# Transmitter-2_4GHz.net
KiCad netlist of a schematic drawn in Altium Designer
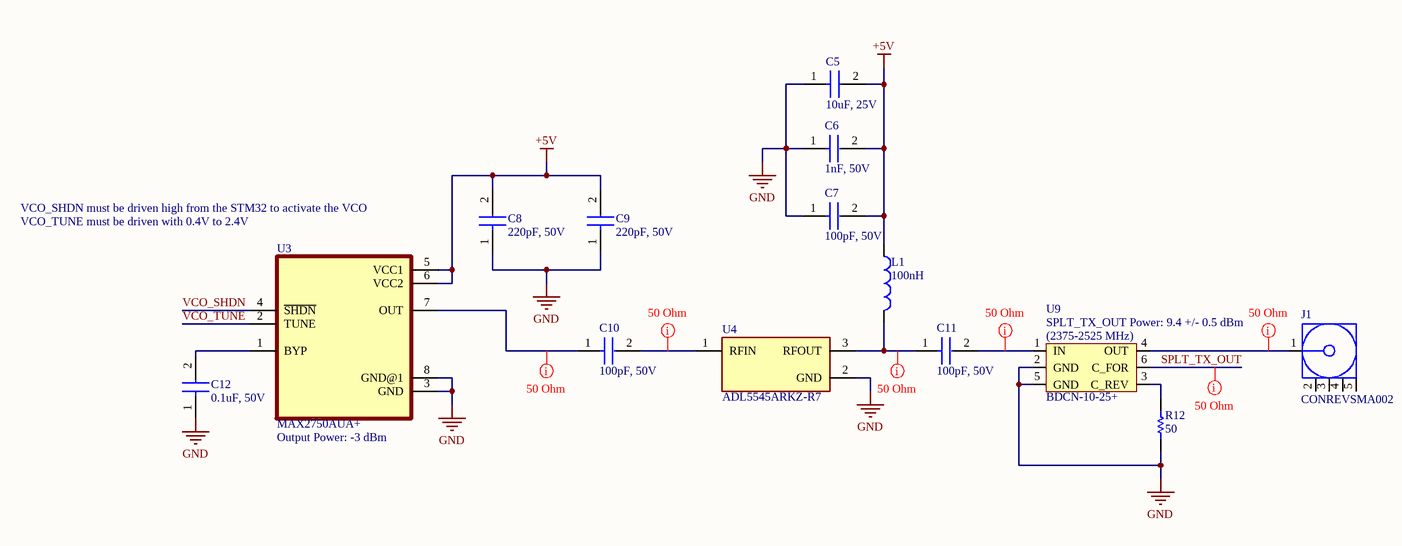
[diagram p0: Transmitter-2.4GHz.SchDoc]

(export (version "E")
  (design (tool "Eeschema 10.0.6"))
  (components
    (comp (ref "C5")
      (value "10uF, 25V")
      (footprint "CAP_CL31_SAM")
      (fields
        (field (name "MANUFACTURER") "Samsung")
        (field (name "MANUFACTURER PART NUMBER") "CL31B106KAHNNNE")
      )
      (libsource (lib "FMCW-Radar-v1") (part "CL31B106KAHNNNE"))
    )
    (comp (ref "C6")
      (value "1nF, 50V")
      (footprint "FP-0603-L_1_6_0_15-W_0_81-IPC_C")
      (fields
        (field (name "MANUFACTURER") "Kyocera AVX")
        (field (name "MANUFACTURER PART NUMBER") "06035A102JAT2A")
      )
      (libsource (lib "FMCW-Radar-v1") (part "06035A102JAT2A"))
    )
    (comp (ref "C7")
      (value "100pF, 50V")
      (footprint "CAPC17595_87N_KEM")
      (fields
        (field (name "MANUFACTURER") "KEMET")
        (field (name "MANUFACTURER PART NUMBER") "C0603C101J5GACTU")
      )
      (libsource (lib "FMCW-Radar-v1") (part "C0603C101J5GACTU"))
    )
    (comp (ref "C8")
      (value "220pF, 50V")
      (footprint "CAPC17595_87N_KEM")
      (fields
        (field (name "MANUFACTURER") "KEMET")
        (field (name "MANUFACTURER PART NUMBER") "C0603C221J5GAC7411")
      )
      (libsource (lib "FMCW-Radar-v1") (part "C0603C221J5GAC7411"))
    )
    (comp (ref "C9")
      (value "220pF, 50V")
      (footprint "CAPC17595_87N_KEM")
      (fields
        (field (name "MANUFACTURER") "KEMET")
        (field (name "MANUFACTURER PART NUMBER") "C0603C221J5GAC7411")
      )
      (libsource (lib "FMCW-Radar-v1") (part "C0603C221J5GAC7411"))
    )
    (comp (ref "C10")
      (value "100pF, 50V")
      (footprint "CAP_CC0402_YAG")
      (fields
        (field (name "MANUFACTURER") "Yageo")
        (field (name "MANUFACTURER PART NUMBER") "CC0402JRNPO9BN101")
      )
      (libsource (lib "FMCW-Radar-v1") (part "CC0402JRNPO9BN101"))
    )
    (comp (ref "C11")
      (value "100pF, 50V")
      (footprint "CAP_CC0402_YAG")
      (fields
        (field (name "MANUFACTURER") "Yageo")
        (field (name "MANUFACTURER PART NUMBER") "CC0402JRNPO9BN101")
      )
      (libsource (lib "FMCW-Radar-v1") (part "CC0402JRNPO9BN101"))
    )
    (comp (ref "C12")
      (value "0.1uF, 50V")
      (footprint "CAP_CC0603_YAG-M")
      (fields
        (field (name "MANUFACTURER") "Yageo")
        (field (name "MANUFACTURER PART NUMBER") "CC0603JRX7R9BB104")
      )
      (libsource (lib "FMCW-Radar-v1") (part "CC0603JRX7R9BB104"))
    )
    (comp (ref "J1")
      (value "CONREVSMA002")
      (footprint "CON-REVSMA-RA")
      (description "RF SMA Connector")
      (fields (field (name "MANUFACTURER") "Linx"))
      (libsource (lib "FMCW-Radar-v1") (part "CONREVSMA002"))
    )
    (comp (ref "L1")
      (value "100nH")
      (footprint "INDC1608X95N")
      (description "General Purpose Inductor, 0.1uH, 5%, 1 Element, Air-Core, SMD, 0603")
      (fields
        (field (name "MANUFACTURER") "Murata")
        (field (name "MANUFACTURER PART NUMBER") "LQG18HNR10J00D")
      )
      (libsource (lib "FMCW-Radar-v1") (part "LQG18HNR10J00D"))
    )
    (comp (ref "R12")
      (value "50")
      (footprint "RESC1005X35N")
      (description "Fixed Resistor, Thin Film, 0.0625W, 50ohm, 50V, 0.1% +/-Tol, 50ppm/Cel, Surface Mount, 0402")
      (fields
        (field (name "MANUFACTURER") "Yageo")
        (field (name "MANUFACTURER PART NUMBER") "RT0402BRE0750RL")
      )
      (libsource (lib "FMCW-Radar-v1") (part "RT0402BRE0750RL"))
    )
    (comp (ref "U3")
      (value "MAX2750AUA+")
      (footprint "SOP65P490X110-8N")
      (description "Voltage Controlled Oscillator, 2370MHz Min, 2470MHz Max")
      (fields (field (name "MANUFACTURER") "Maxim"))
      (libsource (lib "FMCW-Radar-v1") (part "MAX2750AUA+"))
    )
    (comp (ref "U4")
      (value "ADL5545ARKZ-R7")
      (footprint "ADL5545ARKZ-R7")
      (description "Wide Band Medium Power Amplifier, 30MHz Min, 6000MHz Max, 1 Func, BIPolar")
      (fields (field (name "MANUFACTURER") "Analog Devices"))
      (libsource (lib "FMCW-Radar-v1") (part "ADL5545ARKZ-R7"))
    )
    (comp (ref "U9")
      (value "BDCN-10-25+")
      (footprint "BDCN-10-25+")
      (description "Bi-Directional Coupler, 824MHz Min, 2525MHz Max, 1.5dB Insertion Loss-Max")
      (fields (field (name "MANUFACTURER") "Mini-Circuits"))
      (libsource (lib "FMCW-Radar-v1") (part "BDCN-10-25+"))
    )
  )
  (nets
    (net (code "1") (name "+5V") (class "Default")
      (node (ref "C5") (pin "2") (pinfunction "2_2") (pintype "passive"))
      (node (ref "C6") (pin "2") (pinfunction "2_2") (pintype "passive"))
      (node (ref "C7") (pin "2") (pinfunction "2_2") (pintype "passive"))
      (node (ref "C8") (pin "2") (pinfunction "2_2") (pintype "passive"))
      (node (ref "C9") (pin "2") (pinfunction "2_2") (pintype "passive"))
      (node (ref "L1") (pin "1") (pinfunction "1_1") (pintype "passive"))
      (node (ref "U3") (pin "5") (pinfunction "VCC1_5") (pintype "power_in"))
      (node (ref "U3") (pin "6") (pinfunction "VCC2_6") (pintype "power_in"))
    )
    (net (code "2") (name "/SPLT_TX_OUT") (class "Default")
      (node (ref "U9") (pin "6") (pinfunction "C_FOR_6") (pintype "passive"))
    )
    (net (code "3") (name "/VCO_SHDN") (class "Default")
      (node (ref "U3") (pin "4") (pinfunction "~{SHDN}_4") (pintype "passive"))
    )
    (net (code "4") (name "/VCO_TUNE") (class "Default")
      (node (ref "U3") (pin "2") (pinfunction "TUNE_2") (pintype "passive"))
    )
    (net (code "5") (name "GND") (class "Default")
      (node (ref "C12") (pin "1") (pinfunction "1_1") (pintype "passive"))
      (node (ref "C5") (pin "1") (pinfunction "1_1") (pintype "passive"))
      (node (ref "C6") (pin "1") (pinfunction "1_1") (pintype "passive"))
      (node (ref "C7") (pin "1") (pinfunction "1_1") (pintype "passive"))
      (node (ref "C8") (pin "1") (pinfunction "1_1") (pintype "passive"))
      (node (ref "C9") (pin "1") (pinfunction "1_1") (pintype "passive"))
      (node (ref "R12") (pin "1") (pinfunction "1_1") (pintype "passive"))
      (node (ref "U3") (pin "3") (pinfunction "GND_3") (pintype "power_in"))
      (node (ref "U3") (pin "8") (pinfunction "GND@1_8") (pintype "power_in"))
      (node (ref "U4") (pin "2") (pinfunction "GND_2") (pintype "passive"))
      (node (ref "U9") (pin "2") (pinfunction "GND_2") (pintype "passive"))
      (node (ref "U9") (pin "5") (pinfunction "GND_5") (pintype "passive"))
    )
    (net (code "6") (name "Net-(J1-Signal)") (class "Default")
      (node (ref "J1") (pin "1") (pinfunction "Signal_1") (pintype "passive"))
      (node (ref "U9") (pin "4") (pinfunction "OUT_4") (pintype "passive"))
    )
    (net (code "7") (name "Net-(U3-BYP)") (class "Default")
      (node (ref "C12") (pin "2") (pinfunction "2_2") (pintype "passive"))
      (node (ref "U3") (pin "1") (pinfunction "BYP_1") (pintype "passive"))
    )
    (net (code "8") (name "Net-(U3-OUT)") (class "Default")
      (node (ref "C10") (pin "1") (pinfunction "1_1") (pintype "passive"))
      (node (ref "U3") (pin "7") (pinfunction "OUT_7") (pintype "passive"))
    )
    (net (code "9") (name "Net-(U4-RFIN)") (class "Default")
      (node (ref "C10") (pin "2") (pinfunction "2_2") (pintype "passive"))
      (node (ref "U4") (pin "1") (pinfunction "RFIN_1") (pintype "passive"))
    )
    (net (code "10") (name "Net-(U4-RFOUT)") (class "Default")
      (node (ref "C11") (pin "1") (pinfunction "1_1") (pintype "passive"))
      (node (ref "L1") (pin "2") (pinfunction "2_2") (pintype "passive"))
      (node (ref "U4") (pin "3") (pinfunction "RFOUT_3") (pintype "passive"))
    )
    (net (code "11") (name "Net-(U9-C_REV)") (class "Default")
      (node (ref "R12") (pin "2") (pinfunction "2_2") (pintype "passive"))
      (node (ref "U9") (pin "3") (pinfunction "C_REV_3") (pintype "passive"))
    )
    (net (code "12") (name "Net-(U9-IN)") (class "Default")
      (node (ref "C11") (pin "2") (pinfunction "2_2") (pintype "passive"))
      (node (ref "U9") (pin "1") (pinfunction "IN_1") (pintype "passive"))
    )
    (net (code "13") (name "unconnected-(J1-GND-Pad2)") (class "Default")
      (node (ref "J1") (pin "2") (pinfunction "GND_2") (pintype "power_in"))
    )
    (net (code "14") (name "unconnected-(J1-GND-Pad3)") (class "Default")
      (node (ref "J1") (pin "3") (pinfunction "GND_3") (pintype "power_in"))
    )
    (net (code "15") (name "unconnected-(J1-GND-Pad4)") (class "Default")
      (node (ref "J1") (pin "4") (pinfunction "GND_4") (pintype "power_in"))
    )
    (net (code "16") (name "unconnected-(J1-GND-Pad5)") (class "Default")
      (node (ref "J1") (pin "5") (pinfunction "GND_5") (pintype "power_in"))
    )
  )
)
